# PPS_schematic.net
KiCad netlist of a schematic drawn in EAGLE
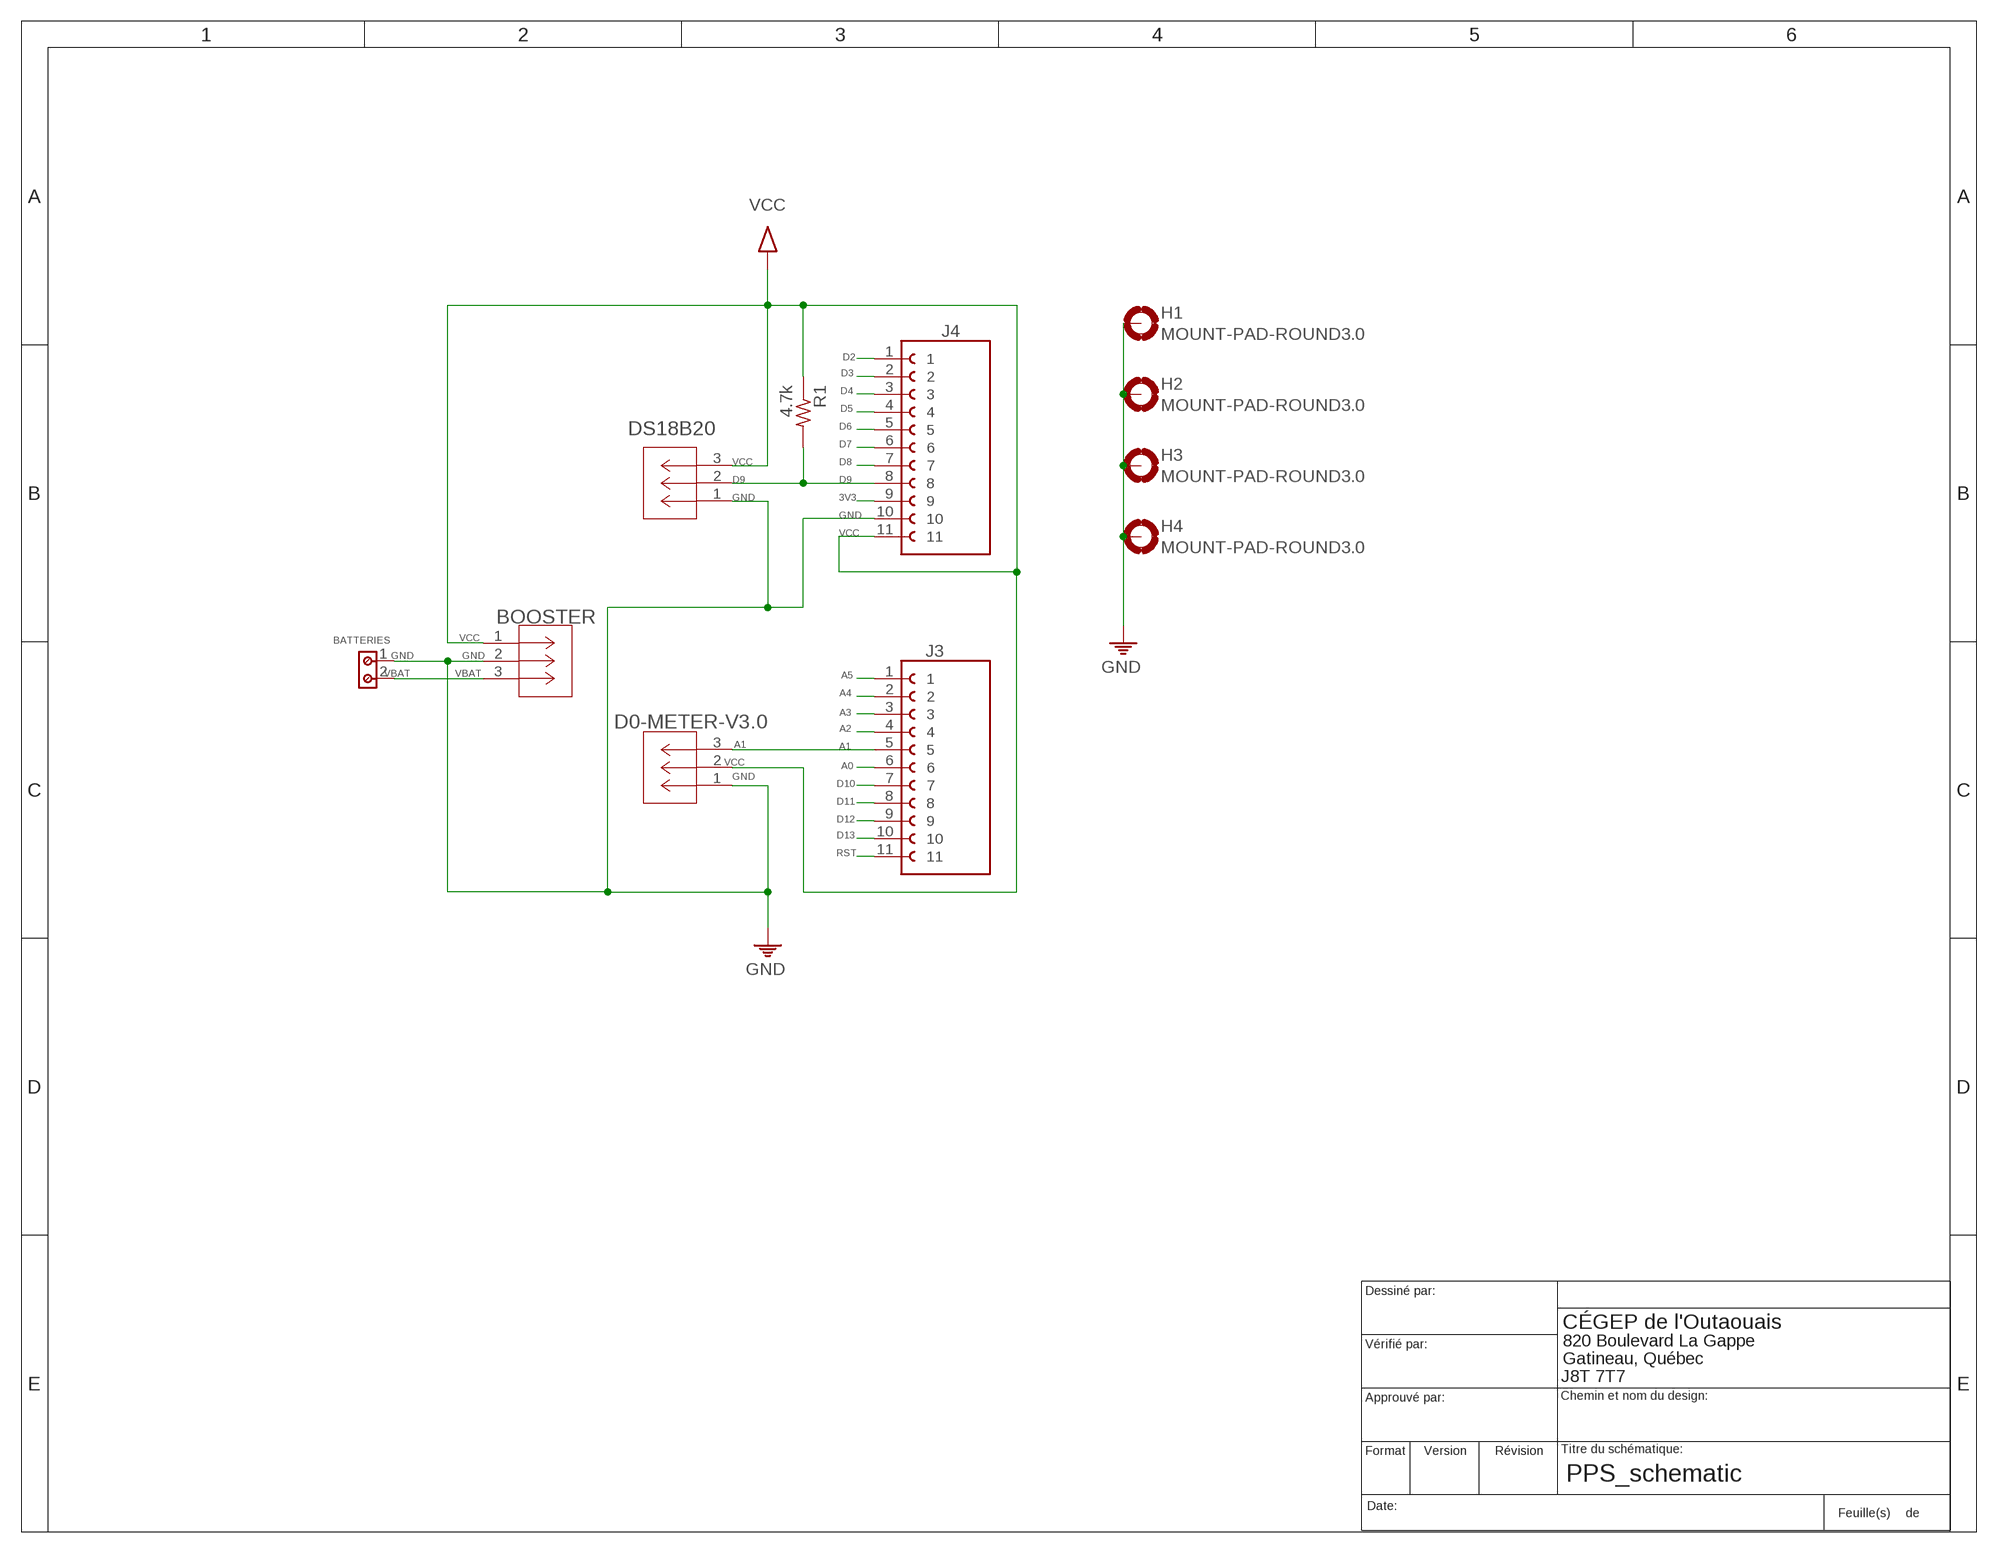
[diagram p0: schematic, sheet 1]

(export (version "E")
  (design (tool "Eeschema 10.0.6"))
  (components
    (comp (ref "BATTERIES")
      (value "691137710002")
      (footprint "eagle-import:691137710002")
      (libsource (lib "eagle-import") (part "691137710002"))
    )
    (comp (ref "BOOSTER")
      (value "TS-103-T-ACON3_1X3_TU_HTS_SAI")
      (footprint "eagle-import:CON3_1X3_TU_HTS_SAI")
      (fields
        (field (name "MANUFACTURER_PART_NUMBER") "TS-103-T-A")
        (field (name "COPYRIGHT") "Copyright (C) 2024 Ultra Librarian. All rights reserved.")
      )
      (libsource (lib "eagle-import") (part "TS-103-T-ACON3_1X3_TU_HTS_SAI"))
    )
    (comp (ref "D0-METER-V3.0")
      (value "PPTC031LFBN-RCCONN_PPTC031_SUL")
      (footprint "eagle-import:CONN_PPTC031_SUL")
      (fields
        (field (name "MANUFACTURER_PART_NUMBER") "PPTC031LFBN-RC")
        (field (name "COPYRIGHT") "Copyright (C) 2024 Ultra Librarian. All rights reserved.")
      )
      (libsource (lib "eagle-import") (part "PPTC031LFBN-RCCONN_PPTC031_SUL"))
    )
    (comp (ref "DS18B20")
      (value "PPTC031LFBN-RCCONN_PPTC031_SUL")
      (footprint "eagle-import:CONN_PPTC031_SUL")
      (fields
        (field (name "MANUFACTURER_PART_NUMBER") "PPTC031LFBN-RC")
        (field (name "COPYRIGHT") "Copyright (C) 2024 Ultra Librarian. All rights reserved.")
      )
      (libsource (lib "eagle-import") (part "PPTC031LFBN-RCCONN_PPTC031_SUL"))
    )
    (comp (ref "H1")
      (value "MOUNT-PAD-ROUND3.0")
      (footprint "eagle-import:3,0-PAD")
      (libsource (lib "eagle-import") (part "MOUNT-PAD-ROUND3.0"))
    )
    (comp (ref "H2")
      (value "MOUNT-PAD-ROUND3.0")
      (footprint "eagle-import:3,0-PAD")
      (libsource (lib "eagle-import") (part "MOUNT-PAD-ROUND3.0"))
    )
    (comp (ref "H3")
      (value "MOUNT-PAD-ROUND3.0")
      (footprint "eagle-import:3,0-PAD")
      (libsource (lib "eagle-import") (part "MOUNT-PAD-ROUND3.0"))
    )
    (comp (ref "H4")
      (value "MOUNT-PAD-ROUND3.0")
      (footprint "eagle-import:3,0-PAD")
      (libsource (lib "eagle-import") (part "MOUNT-PAD-ROUND3.0"))
    )
    (comp (ref "J3")
      (value "M20-7821146")
      (footprint "eagle-import:HARWIN_M20-7821146")
      (fields (field (name "MANUFACTURER") "HARWIN"))
      (libsource (lib "eagle-import") (part "M20-7821146"))
    )
    (comp (ref "J4")
      (value "M20-7821146")
      (footprint "eagle-import:HARWIN_M20-7821146")
      (fields (field (name "MANUFACTURER") "HARWIN"))
      (libsource (lib "eagle-import") (part "M20-7821146"))
    )
    (comp (ref "R1")
      (value "4.7k")
      (footprint "eagle-import:M1206")
      (libsource (lib "eagle-import") (part "RM1206"))
    )
  )
  (nets
    (net (code "1") (name "/3V3") (class "Default")
      (node (ref "J4") (pin "9") (pinfunction "9_9") (pintype "passive"))
    )
    (net (code "2") (name "/A0") (class "Default")
      (node (ref "J3") (pin "6") (pinfunction "6_6") (pintype "passive"))
    )
    (net (code "3") (name "/A1") (class "Default")
      (node (ref "D0-METER-V3.0") (pin "3") (pinfunction "3_3") (pintype "passive"))
      (node (ref "J3") (pin "5") (pinfunction "5_5") (pintype "passive"))
    )
    (net (code "4") (name "/A2") (class "Default")
      (node (ref "J3") (pin "4") (pinfunction "4_4") (pintype "passive"))
    )
    (net (code "5") (name "/A3") (class "Default")
      (node (ref "J3") (pin "3") (pinfunction "3_3") (pintype "passive"))
    )
    (net (code "6") (name "/A4") (class "Default")
      (node (ref "J3") (pin "2") (pinfunction "2_2") (pintype "passive"))
    )
    (net (code "7") (name "/A5") (class "Default")
      (node (ref "J3") (pin "1") (pinfunction "1_1") (pintype "passive"))
    )
    (net (code "8") (name "/D2") (class "Default")
      (node (ref "J4") (pin "1") (pinfunction "1_1") (pintype "passive"))
    )
    (net (code "9") (name "/D3") (class "Default")
      (node (ref "J4") (pin "2") (pinfunction "2_2") (pintype "passive"))
    )
    (net (code "10") (name "/D4") (class "Default")
      (node (ref "J4") (pin "3") (pinfunction "3_3") (pintype "passive"))
    )
    (net (code "11") (name "/D5") (class "Default")
      (node (ref "J4") (pin "4") (pinfunction "4_4") (pintype "passive"))
    )
    (net (code "12") (name "/D6") (class "Default")
      (node (ref "J4") (pin "5") (pinfunction "5_5") (pintype "passive"))
    )
    (net (code "13") (name "/D7") (class "Default")
      (node (ref "J4") (pin "6") (pinfunction "6_6") (pintype "passive"))
    )
    (net (code "14") (name "/D8") (class "Default")
      (node (ref "J4") (pin "7") (pinfunction "7_7") (pintype "passive"))
    )
    (net (code "15") (name "/D9") (class "Default")
      (node (ref "DS18B20") (pin "2") (pinfunction "2_2") (pintype "passive"))
      (node (ref "J4") (pin "8") (pinfunction "8_8") (pintype "passive"))
      (node (ref "R1") (pin "2") (pinfunction "2_2") (pintype "passive"))
    )
    (net (code "16") (name "/D10") (class "Default")
      (node (ref "J3") (pin "7") (pinfunction "7_7") (pintype "passive"))
    )
    (net (code "17") (name "/D11") (class "Default")
      (node (ref "J3") (pin "8") (pinfunction "8_8") (pintype "passive"))
    )
    (net (code "18") (name "/D12") (class "Default")
      (node (ref "J3") (pin "9") (pinfunction "9_9") (pintype "passive"))
    )
    (net (code "19") (name "/D13") (class "Default")
      (node (ref "J3") (pin "10") (pinfunction "10_10") (pintype "passive"))
    )
    (net (code "20") (name "/RST") (class "Default")
      (node (ref "J3") (pin "11") (pinfunction "11_11") (pintype "passive"))
    )
    (net (code "21") (name "/VBAT") (class "Default")
      (node (ref "BATTERIES") (pin "2") (pinfunction "2_2") (pintype "passive"))
      (node (ref "BOOSTER") (pin "3") (pinfunction "3_3") (pintype "passive"))
    )
    (net (code "22") (name "GND") (class "Default")
      (node (ref "BATTERIES") (pin "1") (pinfunction "1_1") (pintype "passive"))
      (node (ref "BOOSTER") (pin "2") (pinfunction "2_2") (pintype "passive"))
      (node (ref "D0-METER-V3.0") (pin "1") (pinfunction "1_1") (pintype "passive"))
      (node (ref "DS18B20") (pin "1") (pinfunction "1_1") (pintype "passive"))
      (node (ref "H1") (pin "B3,0") (pinfunction "MOUNT_B3,0") (pintype "passive"))
      (node (ref "H2") (pin "B3,0") (pinfunction "MOUNT_B3,0") (pintype "passive"))
      (node (ref "H3") (pin "B3,0") (pinfunction "MOUNT_B3,0") (pintype "passive"))
      (node (ref "H4") (pin "B3,0") (pinfunction "MOUNT_B3,0") (pintype "passive"))
      (node (ref "J4") (pin "10") (pinfunction "10_10") (pintype "passive"))
    )
    (net (code "23") (name "VCC") (class "Default")
      (node (ref "BOOSTER") (pin "1") (pinfunction "1_1") (pintype "passive"))
      (node (ref "D0-METER-V3.0") (pin "2") (pinfunction "2_2") (pintype "passive"))
      (node (ref "DS18B20") (pin "3") (pinfunction "3_3") (pintype "passive"))
      (node (ref "J4") (pin "11") (pinfunction "11_11") (pintype "passive"))
      (node (ref "R1") (pin "1") (pinfunction "1_1") (pintype "passive"))
    )
  )
)
